# DE-061116.net
KiCad netlist of a schematic drawn in Altium Designer
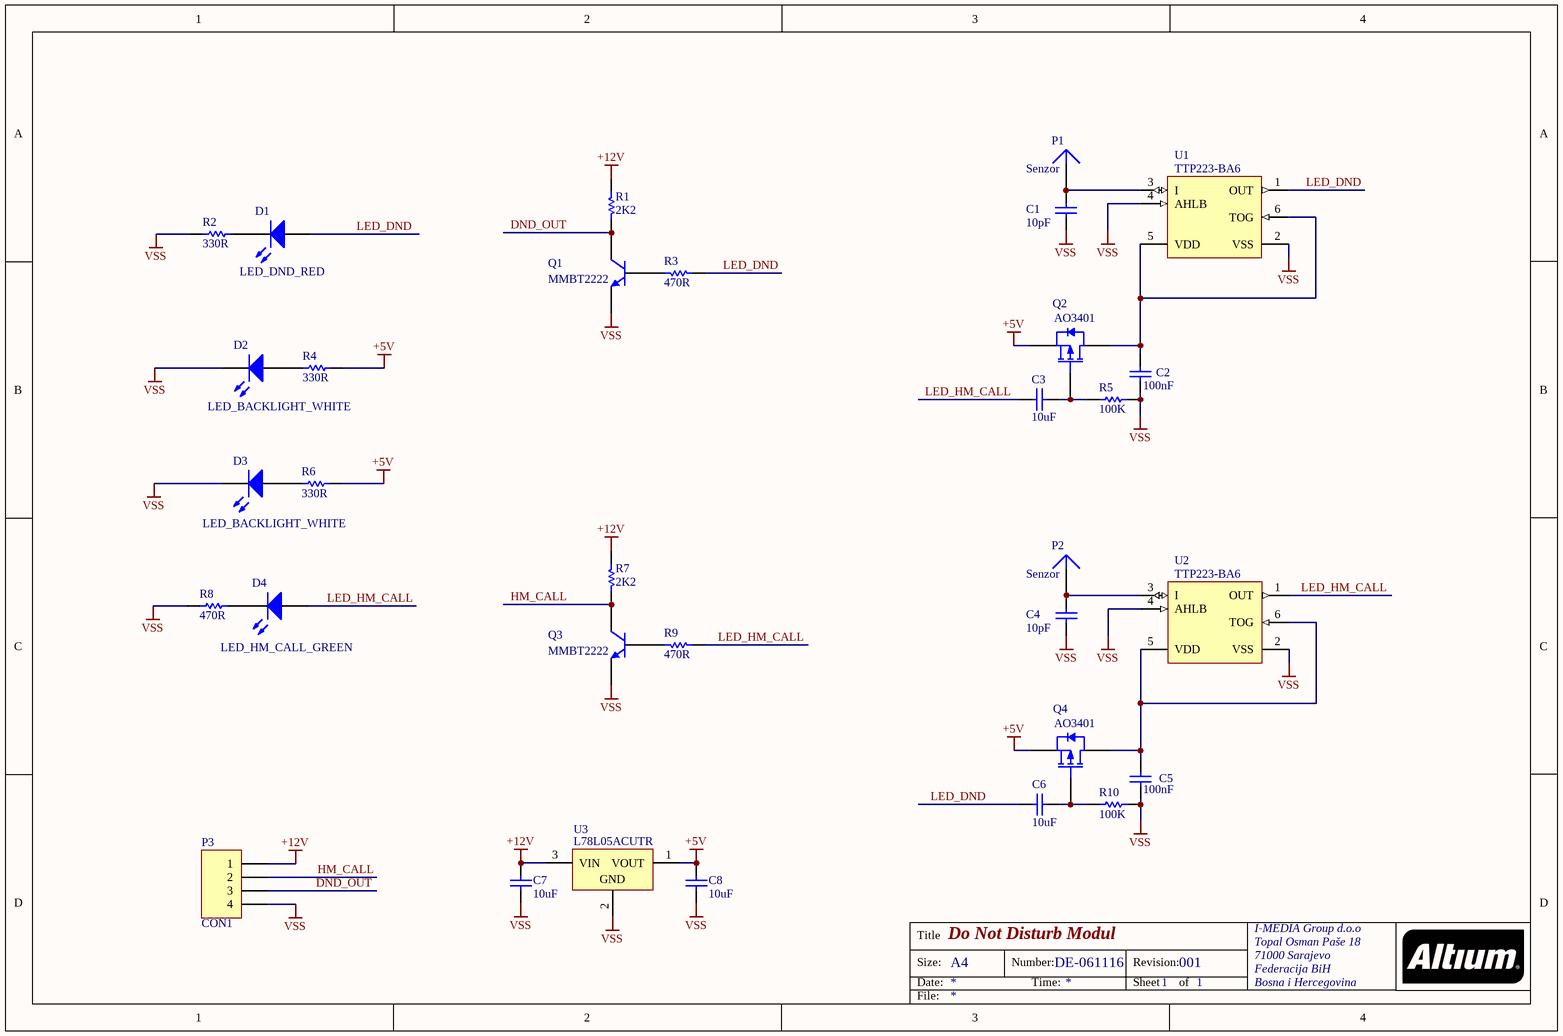
[diagram p0: DE-061116.SchDoc]

(export (version "E")
  (design (tool "Eeschema 10.0.6"))
  (components
    (comp (ref "C1")
      (value "10pF")
      (footprint "0603")
      (description "Ceramic Chip Capacitor - Standard")
      (fields (field (name "PUBLISHER") "Altium Limited"))
      (libsource (lib "KEMET Chip Capacitor") (part "C0603"))
    )
    (comp (ref "C2")
      (value "100nF")
      (footprint "0603")
      (description "Ceramic Chip Capacitor - Standard")
      (fields (field (name "PUBLISHER") "Altium Limited"))
      (libsource (lib "KEMET Chip Capacitor") (part "C0603"))
    )
    (comp (ref "C3")
      (value "10uF")
      (footprint "0805")
      (description "Ceramic Chip Capacitor - Standard")
      (fields (field (name "PUBLISHER") "Altium Limited"))
      (libsource (lib "DE-061116") (part "C0805"))
    )
    (comp (ref "C4")
      (value "10pF")
      (footprint "0603")
      (description "Ceramic Chip Capacitor - Standard")
      (fields (field (name "PUBLISHER") "Altium Limited"))
      (libsource (lib "KEMET Chip Capacitor") (part "C0603"))
    )
    (comp (ref "C5")
      (value "100nF")
      (footprint "0603")
      (description "Ceramic Chip Capacitor - Standard")
      (fields (field (name "PUBLISHER") "Altium Limited"))
      (libsource (lib "KEMET Chip Capacitor") (part "C0603"))
    )
    (comp (ref "C6")
      (value "10uF")
      (footprint "0805")
      (description "Ceramic Chip Capacitor - Standard")
      (fields (field (name "PUBLISHER") "Altium Limited"))
      (libsource (lib "DE-061116") (part "C0805"))
    )
    (comp (ref "C7")
      (value "10uF")
      (footprint "0805")
      (description "Ceramic Chip Capacitor - Standard")
      (fields (field (name "PUBLISHER") "Altium Limited"))
      (libsource (lib "DE-061116") (part "C0805"))
    )
    (comp (ref "C8")
      (value "10uF")
      (footprint "0805")
      (description "Ceramic Chip Capacitor - Standard")
      (fields (field (name "PUBLISHER") "Altium Limited"))
      (libsource (lib "DE-061116") (part "C0805"))
    )
    (comp (ref "D1")
      (value "LED_DND_RED")
      (footprint "2.0X1.25X1.2")
      (description "Top Mount AS AlInGaP Red Oval Lens High Brightness")
      (fields (field (name "PUBLISHER") "Altium Limited"))
      (libsource (lib "Agilent Optoelectronic LED") (part "HSMC-C540-F0001"))
    )
    (comp (ref "D2")
      (value "LED_BACKLIGHT_WHITE")
      (footprint "2.0X1.25X1.2")
      (description "Top Mount AS AlInGaP Red Oval Lens High Brightness")
      (fields (field (name "PUBLISHER") "Altium Limited"))
      (libsource (lib "Agilent Optoelectronic LED") (part "HSMC-C540-F0001"))
    )
    (comp (ref "D3")
      (value "LED_BACKLIGHT_WHITE")
      (footprint "2.0X1.25X1.2")
      (description "Top Mount AS AlInGaP Red Oval Lens High Brightness")
      (fields (field (name "PUBLISHER") "Altium Limited"))
      (libsource (lib "Agilent Optoelectronic LED") (part "HSMC-C540-F0001"))
    )
    (comp (ref "D4")
      (value "LED_HM_CALL_GREEN")
      (footprint "2.0X1.25X1.2")
      (description "Top Mount AS AlInGaP Red Oval Lens High Brightness")
      (fields (field (name "PUBLISHER") "Altium Limited"))
      (libsource (lib "Agilent Optoelectronic LED") (part "HSMC-C540-F0001"))
    )
    (comp (ref "P1")
      (value "Senzor")
      (footprint "PIN1")
      (description "Plug")
      (fields (field (name "PUBLISHER") "Altium Limited"))
      (libsource (lib "Miscellaneous Connectors") (part "Plug"))
    )
    (comp (ref "P2")
      (value "Senzor")
      (footprint "PIN1")
      (description "Plug")
      (fields (field (name "PUBLISHER") "Altium Limited"))
      (libsource (lib "Miscellaneous Connectors") (part "Plug"))
    )
    (comp (ref "P3")
      (value "CON1")
      (footprint "HDR1X4")
      (description "Header, 4-Pin")
      (fields (field (name "PUBLISHER") "Altium Limited"))
      (libsource (lib "Miscellaneous Connectors") (part "Header 4"))
    )
    (comp (ref "Q1")
      (value "MMBT2222")
      (footprint "SOT23_N")
      (description "NPN General-purpose Transistor")
      (fields (field (name "PUBLISHER") "Altium Limited"))
      (libsource (lib "Philips Discrete BJT - Low Power") (part "BC817"))
    )
    (comp (ref "Q2")
      (value "AO3401")
      (footprint "SOT23_N")
      (description "P-channel Enhancement Mode MOSFET")
      (fields (field (name "PUBLISHER") "Altium Limited"))
      (libsource (lib "Philips Discrete MOSFET - Low Power") (part "BSH205"))
    )
    (comp (ref "Q3")
      (value "MMBT2222")
      (footprint "SOT23_N")
      (description "NPN General-purpose Transistor")
      (fields (field (name "PUBLISHER") "Altium Limited"))
      (libsource (lib "Philips Discrete BJT - Low Power") (part "BC817"))
    )
    (comp (ref "Q4")
      (value "AO3401")
      (footprint "SOT23_N")
      (description "P-channel Enhancement Mode MOSFET")
      (fields (field (name "PUBLISHER") "Altium Limited"))
      (libsource (lib "Philips Discrete MOSFET - Low Power") (part "BSH205"))
    )
    (comp (ref "R1")
      (value "2K2")
      (footprint "ERA-0603")
      (fields (field (name "PUBLISHER") "Altium Limited"))
      (libsource (lib "DE-170916") (part "ERAV"))
    )
    (comp (ref "R2")
      (value "330R")
      (footprint "ERA-0603")
      (fields (field (name "PUBLISHER") "Altium Limited"))
      (libsource (lib "DE-170916") (part "ERAV"))
    )
    (comp (ref "R3")
      (value "470R")
      (footprint "ERA-0603")
      (fields (field (name "PUBLISHER") "Altium Limited"))
      (libsource (lib "DE-170916") (part "ERAV"))
    )
    (comp (ref "R4")
      (value "330R")
      (footprint "ERA-0603")
      (fields (field (name "PUBLISHER") "Altium Limited"))
      (libsource (lib "DE-170916") (part "ERAV"))
    )
    (comp (ref "R5")
      (value "100K")
      (footprint "ERA-0603")
      (fields (field (name "PUBLISHER") "Altium Limited"))
      (libsource (lib "DE-151116") (part "ERAV"))
    )
    (comp (ref "R6")
      (value "330R")
      (footprint "ERA-0603")
      (fields (field (name "PUBLISHER") "Altium Limited"))
      (libsource (lib "DE-170916") (part "ERAV"))
    )
    (comp (ref "R7")
      (value "2K2")
      (footprint "ERA-0603")
      (fields (field (name "PUBLISHER") "Altium Limited"))
      (libsource (lib "DE-170916") (part "ERAV"))
    )
    (comp (ref "R8")
      (value "470R")
      (footprint "ERA-0603")
      (fields (field (name "PUBLISHER") "Altium Limited"))
      (libsource (lib "DE-170916") (part "ERAV"))
    )
    (comp (ref "R9")
      (value "470R")
      (footprint "ERA-0603")
      (fields (field (name "PUBLISHER") "Altium Limited"))
      (libsource (lib "DE-170916") (part "ERAV"))
    )
    (comp (ref "R10")
      (value "100K")
      (footprint "ERA-0603")
      (fields (field (name "PUBLISHER") "Altium Limited"))
      (libsource (lib "DE-151116") (part "ERAV"))
    )
    (comp (ref "U1")
      (value "TTP223-BA6")
      (footprint "6ST1_N")
      (description "One-channel Toggle-mode Touch Sensor IC with Power Management Functions, 6-pin SOT23")
      (fields (field (name "PUBLISHER") "Altium Limited"))
      (libsource (lib "Atmel Touch Solutions") (part "AT42QT1012"))
    )
    (comp (ref "U2")
      (value "TTP223-BA6")
      (footprint "6ST1_N")
      (description "One-channel Toggle-mode Touch Sensor IC with Power Management Functions, 6-pin SOT23")
      (fields (field (name "PUBLISHER") "Altium Limited"))
      (libsource (lib "Atmel Touch Solutions") (part "AT42QT1012"))
    )
    (comp (ref "U3")
      (value "L78L05ACUTR")
      (footprint "SOT-89_N")
      (description "Positive Voltage Regulator, 5V, 4-Pin SOT-89, Tape and Reel")
      (libsource (lib "STMicroelectronics Power Management Linear Regulator") (part "L78L05ACUTR"))
    )
  )
  (nets
    (net (code "1") (name "+5V") (class "Default")
      (node (ref "C8") (pin "2") (pinfunction "2_2") (pintype "passive"))
      (node (ref "Q2") (pin "2") (pinfunction "S_2") (pintype "passive"))
      (node (ref "Q4") (pin "2") (pinfunction "S_2") (pintype "passive"))
      (node (ref "R4") (pin "1") (pinfunction "1_1") (pintype "passive"))
      (node (ref "R6") (pin "1") (pinfunction "1_1") (pintype "passive"))
      (node (ref "U3") (pin "1") (pinfunction "VOUT_1") (pintype "power_in"))
    )
    (net (code "2") (name "+12V") (class "Default")
      (node (ref "C7") (pin "2") (pinfunction "2_2") (pintype "passive"))
      (node (ref "P3") (pin "1") (pinfunction "1_1") (pintype "passive"))
      (node (ref "R1") (pin "1") (pinfunction "1_1") (pintype "passive"))
      (node (ref "R7") (pin "1") (pinfunction "1_1") (pintype "passive"))
      (node (ref "U3") (pin "3") (pinfunction "VIN_3") (pintype "power_in"))
    )
    (net (code "3") (name "/DND_OUT") (class "Default")
      (node (ref "P3") (pin "3") (pinfunction "3_3") (pintype "passive"))
      (node (ref "Q1") (pin "3") (pinfunction "C_3") (pintype "passive"))
      (node (ref "R1") (pin "2") (pinfunction "2_2") (pintype "passive"))
    )
    (net (code "4") (name "/HM_CALL") (class "Default")
      (node (ref "P3") (pin "2") (pinfunction "2_2") (pintype "passive"))
      (node (ref "Q3") (pin "3") (pinfunction "C_3") (pintype "passive"))
      (node (ref "R7") (pin "2") (pinfunction "2_2") (pintype "passive"))
    )
    (net (code "5") (name "/LED_DND") (class "Default")
      (node (ref "C6") (pin "1") (pinfunction "1_1") (pintype "passive"))
      (node (ref "D1") (pin "1") (pinfunction "A_1") (pintype "passive"))
      (node (ref "R3") (pin "2") (pinfunction "2_2") (pintype "passive"))
      (node (ref "U1") (pin "1") (pinfunction "OUT_1") (pintype "output"))
    )
    (net (code "6") (name "/LED_HM_CALL") (class "Default")
      (node (ref "C3") (pin "1") (pinfunction "1_1") (pintype "passive"))
      (node (ref "D4") (pin "1") (pinfunction "A_1") (pintype "passive"))
      (node (ref "R9") (pin "2") (pinfunction "2_2") (pintype "passive"))
      (node (ref "U2") (pin "1") (pinfunction "OUT_1") (pintype "output"))
    )
    (net (code "7") (name "Net-(D1-K)") (class "Default")
      (node (ref "D1") (pin "2") (pinfunction "K_2") (pintype "passive"))
      (node (ref "R2") (pin "1") (pinfunction "1_1") (pintype "passive"))
    )
    (net (code "8") (name "Net-(D2-A)") (class "Default")
      (node (ref "D2") (pin "1") (pinfunction "A_1") (pintype "passive"))
      (node (ref "R4") (pin "2") (pinfunction "2_2") (pintype "passive"))
    )
    (net (code "9") (name "Net-(D3-A)") (class "Default")
      (node (ref "D3") (pin "1") (pinfunction "A_1") (pintype "passive"))
      (node (ref "R6") (pin "2") (pinfunction "2_2") (pintype "passive"))
    )
    (net (code "10") (name "Net-(D4-K)") (class "Default")
      (node (ref "D4") (pin "2") (pinfunction "K_2") (pintype "passive"))
      (node (ref "R8") (pin "1") (pinfunction "1_1") (pintype "passive"))
    )
    (net (code "11") (name "Net-(Q1-B)") (class "Default")
      (node (ref "Q1") (pin "1") (pinfunction "B_1") (pintype "passive"))
      (node (ref "R3") (pin "1") (pinfunction "1_1") (pintype "passive"))
    )
    (net (code "12") (name "Net-(Q2-D)") (class "Default")
      (node (ref "C2") (pin "2") (pinfunction "2_2") (pintype "passive"))
      (node (ref "Q2") (pin "3") (pinfunction "D_3") (pintype "passive"))
      (node (ref "U1") (pin "5") (pinfunction "VDD_5") (pintype "power_in"))
      (node (ref "U1") (pin "6") (pinfunction "TOG_6") (pintype "input"))
    )
    (net (code "13") (name "Net-(Q2-G)") (class "Default")
      (node (ref "C3") (pin "2") (pinfunction "2_2") (pintype "passive"))
      (node (ref "Q2") (pin "1") (pinfunction "G_1") (pintype "passive"))
      (node (ref "R5") (pin "2") (pinfunction "2_2") (pintype "passive"))
    )
    (net (code "14") (name "Net-(Q3-B)") (class "Default")
      (node (ref "Q3") (pin "1") (pinfunction "B_1") (pintype "passive"))
      (node (ref "R9") (pin "1") (pinfunction "1_1") (pintype "passive"))
    )
    (net (code "15") (name "Net-(Q4-D)") (class "Default")
      (node (ref "C5") (pin "2") (pinfunction "2_2") (pintype "passive"))
      (node (ref "Q4") (pin "3") (pinfunction "D_3") (pintype "passive"))
      (node (ref "U2") (pin "5") (pinfunction "VDD_5") (pintype "power_in"))
      (node (ref "U2") (pin "6") (pinfunction "TOG_6") (pintype "input"))
    )
    (net (code "16") (name "Net-(Q4-G)") (class "Default")
      (node (ref "C6") (pin "2") (pinfunction "2_2") (pintype "passive"))
      (node (ref "Q4") (pin "1") (pinfunction "G_1") (pintype "passive"))
      (node (ref "R10") (pin "2") (pinfunction "2_2") (pintype "passive"))
    )
    (net (code "17") (name "Net-(U1-I)") (class "Default")
      (node (ref "C1") (pin "1") (pinfunction "1_1") (pintype "passive"))
      (node (ref "P1") (pin "1") (pinfunction "1_1") (pintype "passive"))
      (node (ref "U1") (pin "3") (pinfunction "I_3") (pintype "bidirectional"))
    )
    (net (code "18") (name "Net-(U2-I)") (class "Default")
      (node (ref "C4") (pin "1") (pinfunction "1_1") (pintype "passive"))
      (node (ref "P2") (pin "1") (pinfunction "1_1") (pintype "passive"))
      (node (ref "U2") (pin "3") (pinfunction "I_3") (pintype "bidirectional"))
    )
    (net (code "19") (name "VSS") (class "Default")
      (node (ref "C1") (pin "2") (pinfunction "2_2") (pintype "passive"))
      (node (ref "C2") (pin "1") (pinfunction "1_1") (pintype "passive"))
      (node (ref "C4") (pin "2") (pinfunction "2_2") (pintype "passive"))
      (node (ref "C5") (pin "1") (pinfunction "1_1") (pintype "passive"))
      (node (ref "C7") (pin "1") (pinfunction "1_1") (pintype "passive"))
      (node (ref "C8") (pin "1") (pinfunction "1_1") (pintype "passive"))
      (node (ref "D2") (pin "2") (pinfunction "K_2") (pintype "passive"))
      (node (ref "D3") (pin "2") (pinfunction "K_2") (pintype "passive"))
      (node (ref "P3") (pin "4") (pinfunction "4_4") (pintype "passive"))
      (node (ref "Q1") (pin "2") (pinfunction "E_2") (pintype "passive"))
      (node (ref "Q3") (pin "2") (pinfunction "E_2") (pintype "passive"))
      (node (ref "R10") (pin "1") (pinfunction "1_1") (pintype "passive"))
      (node (ref "R2") (pin "2") (pinfunction "2_2") (pintype "passive"))
      (node (ref "R5") (pin "1") (pinfunction "1_1") (pintype "passive"))
      (node (ref "R8") (pin "2") (pinfunction "2_2") (pintype "passive"))
      (node (ref "U1") (pin "2") (pinfunction "VSS_2") (pintype "power_in"))
      (node (ref "U1") (pin "4") (pinfunction "AHLB_4") (pintype "input"))
      (node (ref "U2") (pin "2") (pinfunction "VSS_2") (pintype "power_in"))
      (node (ref "U2") (pin "4") (pinfunction "AHLB_4") (pintype "input"))
      (node (ref "U3") (pin "2") (pinfunction "GND_2") (pintype "power_in"))
    )
  )
)
